# MicroWordClock2.net
KiCad netlist of a schematic drawn in EAGLE
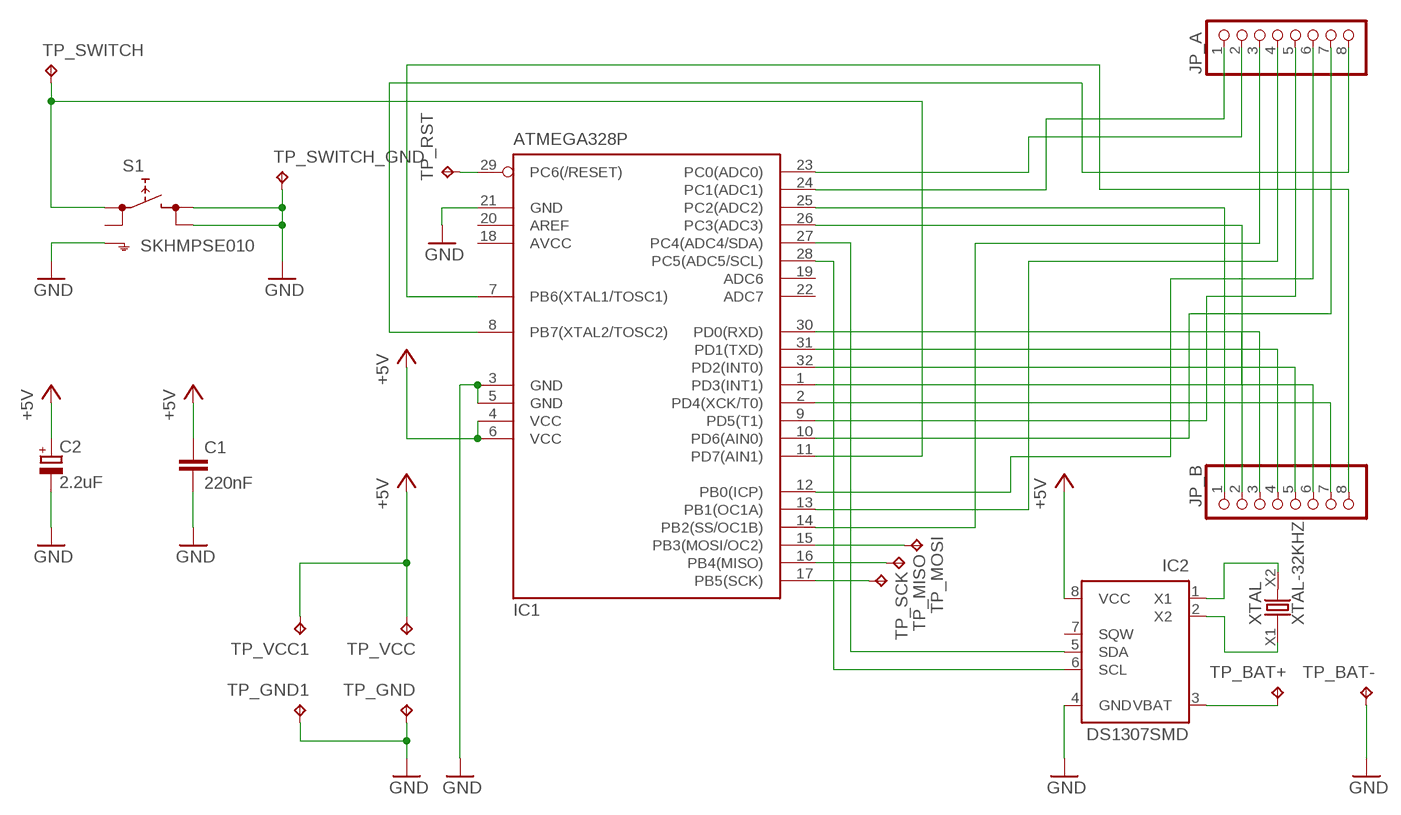
[diagram p0: schematic, sheet 1]

(export (version "E")
  (design (tool "Eeschema 10.0.6"))
  (components
    (comp (ref "C1")
      (value "220nF")
      (footprint "eagle-import:C0805")
      (libsource (lib "eagle-import") (part "C-EUC0805"))
    )
    (comp (ref "C2")
      (value "2.2uF")
      (footprint "eagle-import:B_3528-21R")
      (libsource (lib "eagle-import") (part "CPOL-EUB/3528-21R"))
    )
    (comp (ref "IC1")
      (value "ATMEGA328P")
      (footprint "eagle-import:TQFP32-08")
      (fields (field (name "MPN") "ATMEGA8-16AU"))
      (libsource (lib "eagle-import") (part "MEGA8-AI"))
    )
    (comp (ref "IC2")
      (value "DS1307SMD")
      (footprint "eagle-import:SO-08M")
      (libsource (lib "eagle-import") (part "DS1307SMD"))
    )
    (comp (ref "JP_A")
      (value "PINHD-1X8CLEANBIG")
      (footprint "eagle-import:1X08-CLEANBIG")
      (libsource (lib "eagle-import") (part "PINHD-1X8CLEANBIG"))
    )
    (comp (ref "JP_B")
      (value "PINHD-1X8CLEANBIG")
      (footprint "eagle-import:1X08-CLEANBIG")
      (libsource (lib "eagle-import") (part "PINHD-1X8CLEANBIG"))
    )
    (comp (ref "S1")
      (value "SKHMPSE010")
      (footprint "eagle-import:SKHMPXE010")
      (libsource (lib "eagle-import") (part "SKHMPE010S"))
    )
    (comp (ref "TP_BAT+")
      (value "TPB2,54")
      (footprint "eagle-import:B2,54")
      (libsource (lib "eagle-import") (part "TPB2,54"))
    )
    (comp (ref "TP_BAT-")
      (value "TPB2,54")
      (footprint "eagle-import:B2,54")
      (libsource (lib "eagle-import") (part "TPB2,54"))
    )
    (comp (ref "TP_GND")
      (value "TPB1,27")
      (footprint "eagle-import:B1,27")
      (libsource (lib "eagle-import") (part "TPB1,27"))
    )
    (comp (ref "TP_GND1")
      (value "TPB2,54")
      (footprint "eagle-import:B2,54")
      (libsource (lib "eagle-import") (part "TPB2,54"))
    )
    (comp (ref "TP_MISO")
      (value "TPB1,27")
      (footprint "eagle-import:B1,27")
      (libsource (lib "eagle-import") (part "TPB1,27"))
    )
    (comp (ref "TP_MOSI")
      (value "TPB1,27")
      (footprint "eagle-import:B1,27")
      (libsource (lib "eagle-import") (part "TPB1,27"))
    )
    (comp (ref "TP_RST")
      (value "TPB1,27")
      (footprint "eagle-import:B1,27")
      (libsource (lib "eagle-import") (part "TPB1,27"))
    )
    (comp (ref "TP_SCK")
      (value "TPB1,27")
      (footprint "eagle-import:B1,27")
      (libsource (lib "eagle-import") (part "TPB1,27"))
    )
    (comp (ref "TP_SWITCH")
      (value "TPB1,27")
      (footprint "eagle-import:B1,27")
      (libsource (lib "eagle-import") (part "TPB1,27"))
    )
    (comp (ref "TP_SWITCH_GND")
      (value "TPB1,27")
      (footprint "eagle-import:B1,27")
      (libsource (lib "eagle-import") (part "TPB1,27"))
    )
    (comp (ref "TP_VCC")
      (value "TPB1,27")
      (footprint "eagle-import:B1,27")
      (libsource (lib "eagle-import") (part "TPB1,27"))
    )
    (comp (ref "TP_VCC1")
      (value "TPB2,54")
      (footprint "eagle-import:B2,54")
      (libsource (lib "eagle-import") (part "TPB2,54"))
    )
    (comp (ref "XTAL")
      (value "XTAL-32KHZ")
      (footprint "eagle-import:XTAL-SMD-1206-3216M")
      (libsource (lib "eagle-import") (part "XTAL-32KHZ"))
    )
  )
  (nets
    (net (code "1") (name "+5V") (class "Default")
      (node (ref "C1") (pin "1") (pinfunction "1_1") (pintype "passive"))
      (node (ref "C2") (pin "+") (pinfunction "+_+") (pintype "passive"))
      (node (ref "IC1") (pin "4") (pinfunction "VCC_4") (pintype "power_in"))
      (node (ref "IC1") (pin "6") (pinfunction "VCC_6") (pintype "power_in"))
      (node (ref "IC2") (pin "8") (pinfunction "VCC_8") (pintype "power_in"))
      (node (ref "TP_VCC") (pin "TP") (pinfunction "TP_TP") (pintype "input"))
      (node (ref "TP_VCC1") (pin "TP") (pinfunction "TP_TP") (pintype "input"))
    )
    (net (code "2") (name "/AVCC") (class "Default")
      (node (ref "IC1") (pin "18") (pinfunction "AVCC_18") (pintype "power_in"))
    )
    (net (code "3") (name "GND") (class "Default")
      (node (ref "C1") (pin "2") (pinfunction "2_2") (pintype "passive"))
      (node (ref "C2") (pin "-") (pinfunction "-_-") (pintype "passive"))
      (node (ref "IC1") (pin "21") (pinfunction "GND_21") (pintype "power_in"))
      (node (ref "IC1") (pin "3") (pinfunction "GND_3") (pintype "power_in"))
      (node (ref "IC1") (pin "5") (pinfunction "GND_5") (pintype "power_in"))
      (node (ref "IC2") (pin "4") (pinfunction "GND_4") (pintype "power_in"))
      (node (ref "S1") (pin "3") (pinfunction "2.1_3") (pintype "passive"))
      (node (ref "S1") (pin "4") (pinfunction "2.2_4") (pintype "passive"))
      (node (ref "S1") (pin "5") (pinfunction "SH_5") (pintype "passive"))
      (node (ref "TP_BAT-") (pin "TP") (pinfunction "TP_TP") (pintype "input"))
      (node (ref "TP_GND") (pin "TP") (pinfunction "TP_TP") (pintype "input"))
      (node (ref "TP_GND1") (pin "TP") (pinfunction "TP_TP") (pintype "input"))
      (node (ref "TP_SWITCH_GND") (pin "TP") (pinfunction "TP_TP") (pintype "input"))
    )
    (net (code "4") (name "Net-(IC1-PB0(ICP))") (class "Default")
      (node (ref "IC1") (pin "12") (pinfunction "PB0(ICP)_12") (pintype "bidirectional"))
      (node (ref "JP_A") (pin "6") (pinfunction "6_6") (pintype "passive"))
    )
    (net (code "5") (name "Net-(IC1-PB1(OC1A))") (class "Default")
      (node (ref "IC1") (pin "13") (pinfunction "PB1(OC1A)_13") (pintype "bidirectional"))
      (node (ref "JP_A") (pin "4") (pinfunction "4_4") (pintype "passive"))
    )
    (net (code "6") (name "Net-(IC1-PB2(SS{slash}OC1B))") (class "Default")
      (node (ref "IC1") (pin "14") (pinfunction "PB2(SS/OC1B)_14") (pintype "bidirectional"))
      (node (ref "JP_A") (pin "3") (pinfunction "3_3") (pintype "passive"))
    )
    (net (code "7") (name "Net-(IC1-PB3(MOSI{slash}OC2))") (class "Default")
      (node (ref "IC1") (pin "15") (pinfunction "PB3(MOSI/OC2)_15") (pintype "bidirectional"))
      (node (ref "TP_MOSI") (pin "TP") (pinfunction "TP_TP") (pintype "input"))
    )
    (net (code "8") (name "Net-(IC1-PB4(MISO))") (class "Default")
      (node (ref "IC1") (pin "16") (pinfunction "PB4(MISO)_16") (pintype "bidirectional"))
      (node (ref "TP_MISO") (pin "TP") (pinfunction "TP_TP") (pintype "input"))
    )
    (net (code "9") (name "Net-(IC1-PB5(SCK))") (class "Default")
      (node (ref "IC1") (pin "17") (pinfunction "PB5(SCK)_17") (pintype "bidirectional"))
      (node (ref "TP_SCK") (pin "TP") (pinfunction "TP_TP") (pintype "input"))
    )
    (net (code "10") (name "Net-(IC1-PB6(XTAL1{slash}TOSC1))") (class "Default")
      (node (ref "IC1") (pin "7") (pinfunction "PB6(XTAL1/TOSC1)_7") (pintype "bidirectional"))
      (node (ref "JP_B") (pin "8") (pinfunction "8_8") (pintype "passive"))
    )
    (net (code "11") (name "Net-(IC1-PB7(XTAL2{slash}TOSC2))") (class "Default")
      (node (ref "IC1") (pin "8") (pinfunction "PB7(XTAL2/TOSC2)_8") (pintype "bidirectional"))
      (node (ref "JP_A") (pin "8") (pinfunction "8_8") (pintype "passive"))
    )
    (net (code "12") (name "Net-(IC1-PC0(ADC0))") (class "Default")
      (node (ref "IC1") (pin "23") (pinfunction "PC0(ADC0)_23") (pintype "bidirectional"))
      (node (ref "JP_A") (pin "2") (pinfunction "2_2") (pintype "passive"))
    )
    (net (code "13") (name "Net-(IC1-PC1(ADC1))") (class "Default")
      (node (ref "IC1") (pin "24") (pinfunction "PC1(ADC1)_24") (pintype "bidirectional"))
      (node (ref "JP_A") (pin "1") (pinfunction "1_1") (pintype "passive"))
    )
    (net (code "14") (name "Net-(IC1-PC2(ADC2))") (class "Default")
      (node (ref "IC1") (pin "25") (pinfunction "PC2(ADC2)_25") (pintype "bidirectional"))
      (node (ref "JP_B") (pin "1") (pinfunction "1_1") (pintype "passive"))
    )
    (net (code "15") (name "Net-(IC1-PC3(ADC3))") (class "Default")
      (node (ref "IC1") (pin "26") (pinfunction "PC3(ADC3)_26") (pintype "bidirectional"))
      (node (ref "JP_B") (pin "2") (pinfunction "2_2") (pintype "passive"))
    )
    (net (code "16") (name "Net-(IC1-PC4(ADC4{slash}SDA))") (class "Default")
      (node (ref "IC1") (pin "27") (pinfunction "PC4(ADC4/SDA)_27") (pintype "bidirectional"))
      (node (ref "IC2") (pin "5") (pinfunction "SDA_5") (pintype "output"))
    )
    (net (code "17") (name "Net-(IC1-PC5(ADC5{slash}SCL))") (class "Default")
      (node (ref "IC1") (pin "28") (pinfunction "PC5(ADC5/SCL)_28") (pintype "bidirectional"))
      (node (ref "IC2") (pin "6") (pinfunction "SCL_6") (pintype "input"))
    )
    (net (code "18") (name "Net-(IC1-PC6({slash}RESET))") (class "Default")
      (node (ref "IC1") (pin "29") (pinfunction "PC6(/RESET)_29") (pintype "bidirectional"))
      (node (ref "TP_RST") (pin "TP") (pinfunction "TP_TP") (pintype "input"))
    )
    (net (code "19") (name "Net-(IC1-PD0(RXD))") (class "Default")
      (node (ref "IC1") (pin "30") (pinfunction "PD0(RXD)_30") (pintype "bidirectional"))
      (node (ref "JP_B") (pin "3") (pinfunction "3_3") (pintype "passive"))
    )
    (net (code "20") (name "Net-(IC1-PD1(TXD))") (class "Default")
      (node (ref "IC1") (pin "31") (pinfunction "PD1(TXD)_31") (pintype "bidirectional"))
      (node (ref "JP_B") (pin "4") (pinfunction "4_4") (pintype "passive"))
    )
    (net (code "21") (name "Net-(IC1-PD2(INT0))") (class "Default")
      (node (ref "IC1") (pin "32") (pinfunction "PD2(INT0)_32") (pintype "bidirectional"))
      (node (ref "JP_B") (pin "5") (pinfunction "5_5") (pintype "passive"))
    )
    (net (code "22") (name "Net-(IC1-PD3(INT1))") (class "Default")
      (node (ref "IC1") (pin "1") (pinfunction "PD3(INT1)_1") (pintype "bidirectional"))
      (node (ref "JP_B") (pin "6") (pinfunction "6_6") (pintype "passive"))
    )
    (net (code "23") (name "Net-(IC1-PD4(XCK{slash}T0))") (class "Default")
      (node (ref "IC1") (pin "2") (pinfunction "PD4(XCK/T0)_2") (pintype "bidirectional"))
      (node (ref "JP_B") (pin "7") (pinfunction "7_7") (pintype "passive"))
    )
    (net (code "24") (name "Net-(IC1-PD5(T1))") (class "Default")
      (node (ref "IC1") (pin "9") (pinfunction "PD5(T1)_9") (pintype "bidirectional"))
      (node (ref "JP_A") (pin "5") (pinfunction "5_5") (pintype "passive"))
    )
    (net (code "25") (name "Net-(IC1-PD6(AIN0))") (class "Default")
      (node (ref "IC1") (pin "10") (pinfunction "PD6(AIN0)_10") (pintype "bidirectional"))
      (node (ref "JP_A") (pin "7") (pinfunction "7_7") (pintype "passive"))
    )
    (net (code "26") (name "Net-(IC1-PD7(AIN1))") (class "Default")
      (node (ref "IC1") (pin "11") (pinfunction "PD7(AIN1)_11") (pintype "bidirectional"))
      (node (ref "S1") (pin "1") (pinfunction "1.1_1") (pintype "passive"))
      (node (ref "TP_SWITCH") (pin "TP") (pinfunction "TP_TP") (pintype "input"))
    )
    (net (code "27") (name "Net-(IC2-VBAT)") (class "Default")
      (node (ref "IC2") (pin "3") (pinfunction "VBAT_3") (pintype "input"))
      (node (ref "TP_BAT+") (pin "TP") (pinfunction "TP_TP") (pintype "input"))
    )
    (net (code "28") (name "Net-(IC2-X1)") (class "Default")
      (node (ref "IC2") (pin "1") (pinfunction "X1_1") (pintype "input"))
      (node (ref "XTAL") (pin "X2") (pinfunction "X2_X2") (pintype "passive"))
    )
    (net (code "29") (name "Net-(IC2-X2)") (class "Default")
      (node (ref "IC2") (pin "2") (pinfunction "X2_2") (pintype "input"))
      (node (ref "XTAL") (pin "X1") (pinfunction "X1_X1") (pintype "passive"))
    )
    (net (code "30") (name "unconnected-(IC1-ADC6-Pad19)") (class "Default")
      (node (ref "IC1") (pin "19") (pinfunction "ADC6_19") (pintype "bidirectional"))
    )
    (net (code "31") (name "unconnected-(IC1-ADC7-Pad22)") (class "Default")
      (node (ref "IC1") (pin "22") (pinfunction "ADC7_22") (pintype "bidirectional"))
    )
    (net (code "32") (name "unconnected-(IC1-AREF-Pad20)") (class "Default")
      (node (ref "IC1") (pin "20") (pinfunction "AREF_20") (pintype "passive"))
    )
    (net (code "33") (name "unconnected-(IC2-SQW-Pad7)") (class "Default")
      (node (ref "IC2") (pin "7") (pinfunction "SQW_7") (pintype "input"))
    )
    (net (code "34") (name "unconnected-(S1-1.2-Pad2)") (class "Default")
      (node (ref "S1") (pin "2") (pinfunction "1.2_2") (pintype "passive"))
    )
  )
)
